# teensy_connector_smt_print.net
KiCad netlist of a schematic drawn in EAGLE
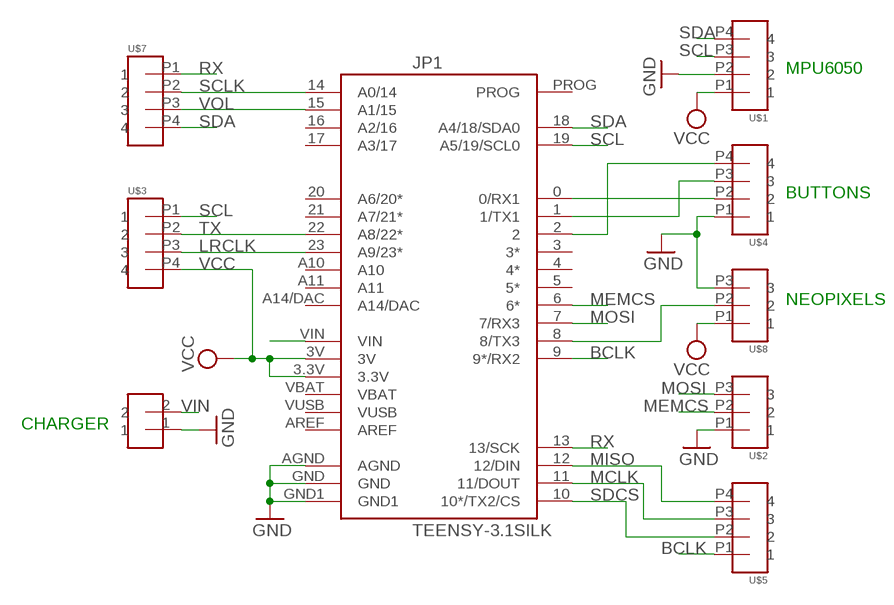
[diagram p0: schematic, sheet 1]

(export (version "E")
  (design (tool "Eeschema 10.0.6"))
  (components
    (comp (ref "JP1")
      (value "TEENSY-3.1SILK")
      (footprint "eagle-import:TEENSY-3.1")
      (libsource (lib "eagle-import") (part "TEENSY-3.1SILK"))
    )
    (comp (ref "U$1")
      (value "PTSM0,4-HH-2,5-SMD-R44")
      (footprint "eagle-import:M04_SMD_RIGHT")
      (libsource (lib "eagle-import") (part "PTSM0,4-HH-2,5-SMD-R44"))
    )
    (comp (ref "U$2")
      (value "PTSM0,3-HH-2,5-SMD-R44")
      (footprint "eagle-import:M03_SMD_RIGHT")
      (libsource (lib "eagle-import") (part "PTSM0,3-HH-2,5-SMD-R44"))
    )
    (comp (ref "U$3")
      (value "PTSM0,4-HH-2,5-SMD-R44")
      (footprint "eagle-import:M04_SMD_RIGHT")
      (libsource (lib "eagle-import") (part "PTSM0,4-HH-2,5-SMD-R44"))
    )
    (comp (ref "U$4")
      (value "PTSM0,4-HH-2,5-SMD-R44")
      (footprint "eagle-import:M04_SMD_RIGHT")
      (libsource (lib "eagle-import") (part "PTSM0,4-HH-2,5-SMD-R44"))
    )
    (comp (ref "U$5")
      (value "PTSM0,4-HH-2,5-SMD-R44")
      (footprint "eagle-import:M04_SMD_RIGHT")
      (libsource (lib "eagle-import") (part "PTSM0,4-HH-2,5-SMD-R44"))
    )
    (comp (ref "U$6")
      (value "HEADER-2")
      (footprint "eagle-import:HEADER-2")
      (libsource (lib "eagle-import") (part "HEADER-2"))
    )
    (comp (ref "U$7")
      (value "PTSM0,4-HH-2,5-SMD-R44")
      (footprint "eagle-import:M04_SMD_RIGHT")
      (libsource (lib "eagle-import") (part "PTSM0,4-HH-2,5-SMD-R44"))
    )
    (comp (ref "U$8")
      (value "PTSM0,3-HH-2,5-SMD-R44")
      (footprint "eagle-import:M03_SMD_RIGHT")
      (libsource (lib "eagle-import") (part "PTSM0,3-HH-2,5-SMD-R44"))
    )
  )
  (nets
    (net (code "1") (name "/BCLK") (class "Default")
      (node (ref "JP1") (pin "9") (pinfunction "9*/RX2_9") (pintype "bidirectional"))
      (node (ref "U$5") (pin "P1") (pinfunction "1_P1") (pintype "bidirectional"))
    )
    (net (code "2") (name "/LRCLK") (class "Default")
      (node (ref "JP1") (pin "23") (pinfunction "A9/23*_23") (pintype "bidirectional"))
      (node (ref "U$3") (pin "P3") (pinfunction "3_P3") (pintype "bidirectional"))
    )
    (net (code "3") (name "/MCLK") (class "Default")
      (node (ref "JP1") (pin "11") (pinfunction "11/DOUT_11") (pintype "bidirectional"))
      (node (ref "U$5") (pin "P3") (pinfunction "3_P3") (pintype "bidirectional"))
    )
    (net (code "4") (name "/MEMCS") (class "Default")
      (node (ref "JP1") (pin "6") (pinfunction "6*_6") (pintype "bidirectional"))
      (node (ref "U$2") (pin "P2") (pinfunction "2_P2") (pintype "bidirectional"))
    )
    (net (code "5") (name "/MISO") (class "Default")
      (node (ref "JP1") (pin "12") (pinfunction "12/DIN_12") (pintype "bidirectional"))
      (node (ref "U$5") (pin "P4") (pinfunction "4_P4") (pintype "bidirectional"))
    )
    (net (code "6") (name "/MOSI") (class "Default")
      (node (ref "JP1") (pin "7") (pinfunction "7/RX3_7") (pintype "bidirectional"))
      (node (ref "U$2") (pin "P3") (pinfunction "3_P3") (pintype "bidirectional"))
    )
    (net (code "7") (name "/RX") (class "Default")
      (node (ref "JP1") (pin "13") (pinfunction "13/SCK_13") (pintype "bidirectional"))
      (node (ref "U$7") (pin "P1") (pinfunction "1_P1") (pintype "bidirectional"))
    )
    (net (code "8") (name "/SCL") (class "Default")
      (node (ref "JP1") (pin "19") (pinfunction "A5/19/SCL0_19") (pintype "bidirectional"))
      (node (ref "U$1") (pin "P3") (pinfunction "3_P3") (pintype "bidirectional"))
      (node (ref "U$3") (pin "P1") (pinfunction "1_P1") (pintype "bidirectional"))
    )
    (net (code "9") (name "/SCLK") (class "Default")
      (node (ref "JP1") (pin "14") (pinfunction "A0/14_14") (pintype "bidirectional"))
      (node (ref "U$7") (pin "P2") (pinfunction "2_P2") (pintype "bidirectional"))
    )
    (net (code "10") (name "/SDA") (class "Default")
      (node (ref "JP1") (pin "18") (pinfunction "A4/18/SDA0_18") (pintype "bidirectional"))
      (node (ref "U$1") (pin "P4") (pinfunction "4_P4") (pintype "bidirectional"))
      (node (ref "U$7") (pin "P4") (pinfunction "4_P4") (pintype "bidirectional"))
    )
    (net (code "11") (name "/SDCS") (class "Default")
      (node (ref "JP1") (pin "10") (pinfunction "10*/TX2/CS_10") (pintype "bidirectional"))
      (node (ref "U$5") (pin "P2") (pinfunction "2_P2") (pintype "bidirectional"))
    )
    (net (code "12") (name "/TX") (class "Default")
      (node (ref "JP1") (pin "22") (pinfunction "A8/22*_22") (pintype "bidirectional"))
      (node (ref "U$3") (pin "P2") (pinfunction "2_P2") (pintype "bidirectional"))
    )
    (net (code "13") (name "/VIN") (class "Default")
      (node (ref "JP1") (pin "VIN") (pinfunction "VIN_VIN") (pintype "bidirectional"))
      (node (ref "U$6") (pin "2") (pinfunction "2_2") (pintype "bidirectional"))
    )
    (net (code "14") (name "/VOL") (class "Default")
      (node (ref "JP1") (pin "15") (pinfunction "A1/15_15") (pintype "bidirectional"))
      (node (ref "U$7") (pin "P3") (pinfunction "3_P3") (pintype "bidirectional"))
    )
    (net (code "15") (name "GND") (class "Default")
      (node (ref "JP1") (pin "AGND") (pinfunction "AGND_AGND") (pintype "bidirectional"))
      (node (ref "JP1") (pin "GND") (pinfunction "GND_GND") (pintype "bidirectional"))
      (node (ref "JP1") (pin "GND1") (pinfunction "GND1_GND1") (pintype "bidirectional"))
      (node (ref "U$1") (pin "P2") (pinfunction "2_P2") (pintype "bidirectional"))
      (node (ref "U$2") (pin "P1") (pinfunction "1_P1") (pintype "bidirectional"))
      (node (ref "U$4") (pin "P1") (pinfunction "1_P1") (pintype "bidirectional"))
      (node (ref "U$6") (pin "1") (pinfunction "1_1") (pintype "bidirectional"))
      (node (ref "U$8") (pin "P3") (pinfunction "3_P3") (pintype "bidirectional"))
    )
    (net (code "16") (name "Net-(JP1-0{slash}RX1)") (class "Default")
      (node (ref "JP1") (pin "0") (pinfunction "0/RX1_0") (pintype "bidirectional"))
      (node (ref "U$4") (pin "P2") (pinfunction "2_P2") (pintype "bidirectional"))
    )
    (net (code "17") (name "Net-(JP1-1{slash}TX1)") (class "Default")
      (node (ref "JP1") (pin "1") (pinfunction "1/TX1_1") (pintype "bidirectional"))
      (node (ref "U$4") (pin "P3") (pinfunction "3_P3") (pintype "bidirectional"))
    )
    (net (code "18") (name "Net-(JP1-8{slash}TX3)") (class "Default")
      (node (ref "JP1") (pin "8") (pinfunction "8/TX3_8") (pintype "bidirectional"))
      (node (ref "U$8") (pin "P2") (pinfunction "2_P2") (pintype "bidirectional"))
    )
    (net (code "19") (name "Net-(U$4-4)") (class "Default")
      (node (ref "JP1") (pin "2") (pinfunction "2_2") (pintype "bidirectional"))
      (node (ref "U$4") (pin "P4") (pinfunction "4_P4") (pintype "bidirectional"))
    )
    (net (code "20") (name "VCC") (class "Default")
      (node (ref "JP1") (pin "3.3V") (pinfunction "3.3V_3.3V") (pintype "bidirectional"))
      (node (ref "JP1") (pin "3V") (pinfunction "3V_3V") (pintype "bidirectional"))
      (node (ref "U$1") (pin "P1") (pinfunction "1_P1") (pintype "bidirectional"))
      (node (ref "U$3") (pin "P4") (pinfunction "4_P4") (pintype "bidirectional"))
      (node (ref "U$8") (pin "P1") (pinfunction "1_P1") (pintype "bidirectional"))
    )
    (net (code "21") (name "unconnected-(JP1-3*-Pad3)") (class "Default")
      (node (ref "JP1") (pin "3") (pinfunction "3*_3") (pintype "bidirectional"))
    )
    (net (code "22") (name "unconnected-(JP1-4*-Pad4)") (class "Default")
      (node (ref "JP1") (pin "4") (pinfunction "4*_4") (pintype "bidirectional"))
    )
    (net (code "23") (name "unconnected-(JP1-5*-Pad5)") (class "Default")
      (node (ref "JP1") (pin "5") (pinfunction "5*_5") (pintype "bidirectional"))
    )
    (net (code "24") (name "unconnected-(JP1-A2{slash}16-Pad16)") (class "Default")
      (node (ref "JP1") (pin "16") (pinfunction "A2/16_16") (pintype "bidirectional"))
    )
    (net (code "25") (name "unconnected-(JP1-A3{slash}17-Pad17)") (class "Default")
      (node (ref "JP1") (pin "17") (pinfunction "A3/17_17") (pintype "bidirectional"))
    )
    (net (code "26") (name "unconnected-(JP1-A6{slash}20*-Pad20)") (class "Default")
      (node (ref "JP1") (pin "20") (pinfunction "A6/20*_20") (pintype "bidirectional"))
    )
    (net (code "27") (name "unconnected-(JP1-A7{slash}21*-Pad21)") (class "Default")
      (node (ref "JP1") (pin "21") (pinfunction "A7/21*_21") (pintype "bidirectional"))
    )
    (net (code "28") (name "unconnected-(JP1-PadA10)") (class "Default")
      (node (ref "JP1") (pin "A10") (pinfunction "A10_A10") (pintype "bidirectional"))
    )
    (net (code "29") (name "unconnected-(JP1-PadA11)") (class "Default")
      (node (ref "JP1") (pin "A11") (pinfunction "A11_A11") (pintype "bidirectional"))
    )
    (net (code "30") (name "unconnected-(JP1-PadA14{slash}DAC)") (class "Default")
      (node (ref "JP1") (pin "A14/DAC") (pinfunction "A14/DAC_A14/DAC") (pintype "bidirectional"))
    )
    (net (code "31") (name "unconnected-(JP1-PadAREF)") (class "Default")
      (node (ref "JP1") (pin "AREF") (pinfunction "AREF_AREF") (pintype "bidirectional"))
    )
    (net (code "32") (name "unconnected-(JP1-PadPROG)") (class "Default")
      (node (ref "JP1") (pin "PROG") (pinfunction "PROG_PROG") (pintype "bidirectional"))
    )
    (net (code "33") (name "unconnected-(JP1-PadVBAT)") (class "Default")
      (node (ref "JP1") (pin "VBAT") (pinfunction "VBAT_VBAT") (pintype "bidirectional"))
    )
    (net (code "34") (name "unconnected-(JP1-PadVUSB)") (class "Default")
      (node (ref "JP1") (pin "VUSB") (pinfunction "VUSB_VUSB") (pintype "bidirectional"))
    )
  )
)
